# led-heart.net
KiCad netlist of a schematic drawn in EAGLE
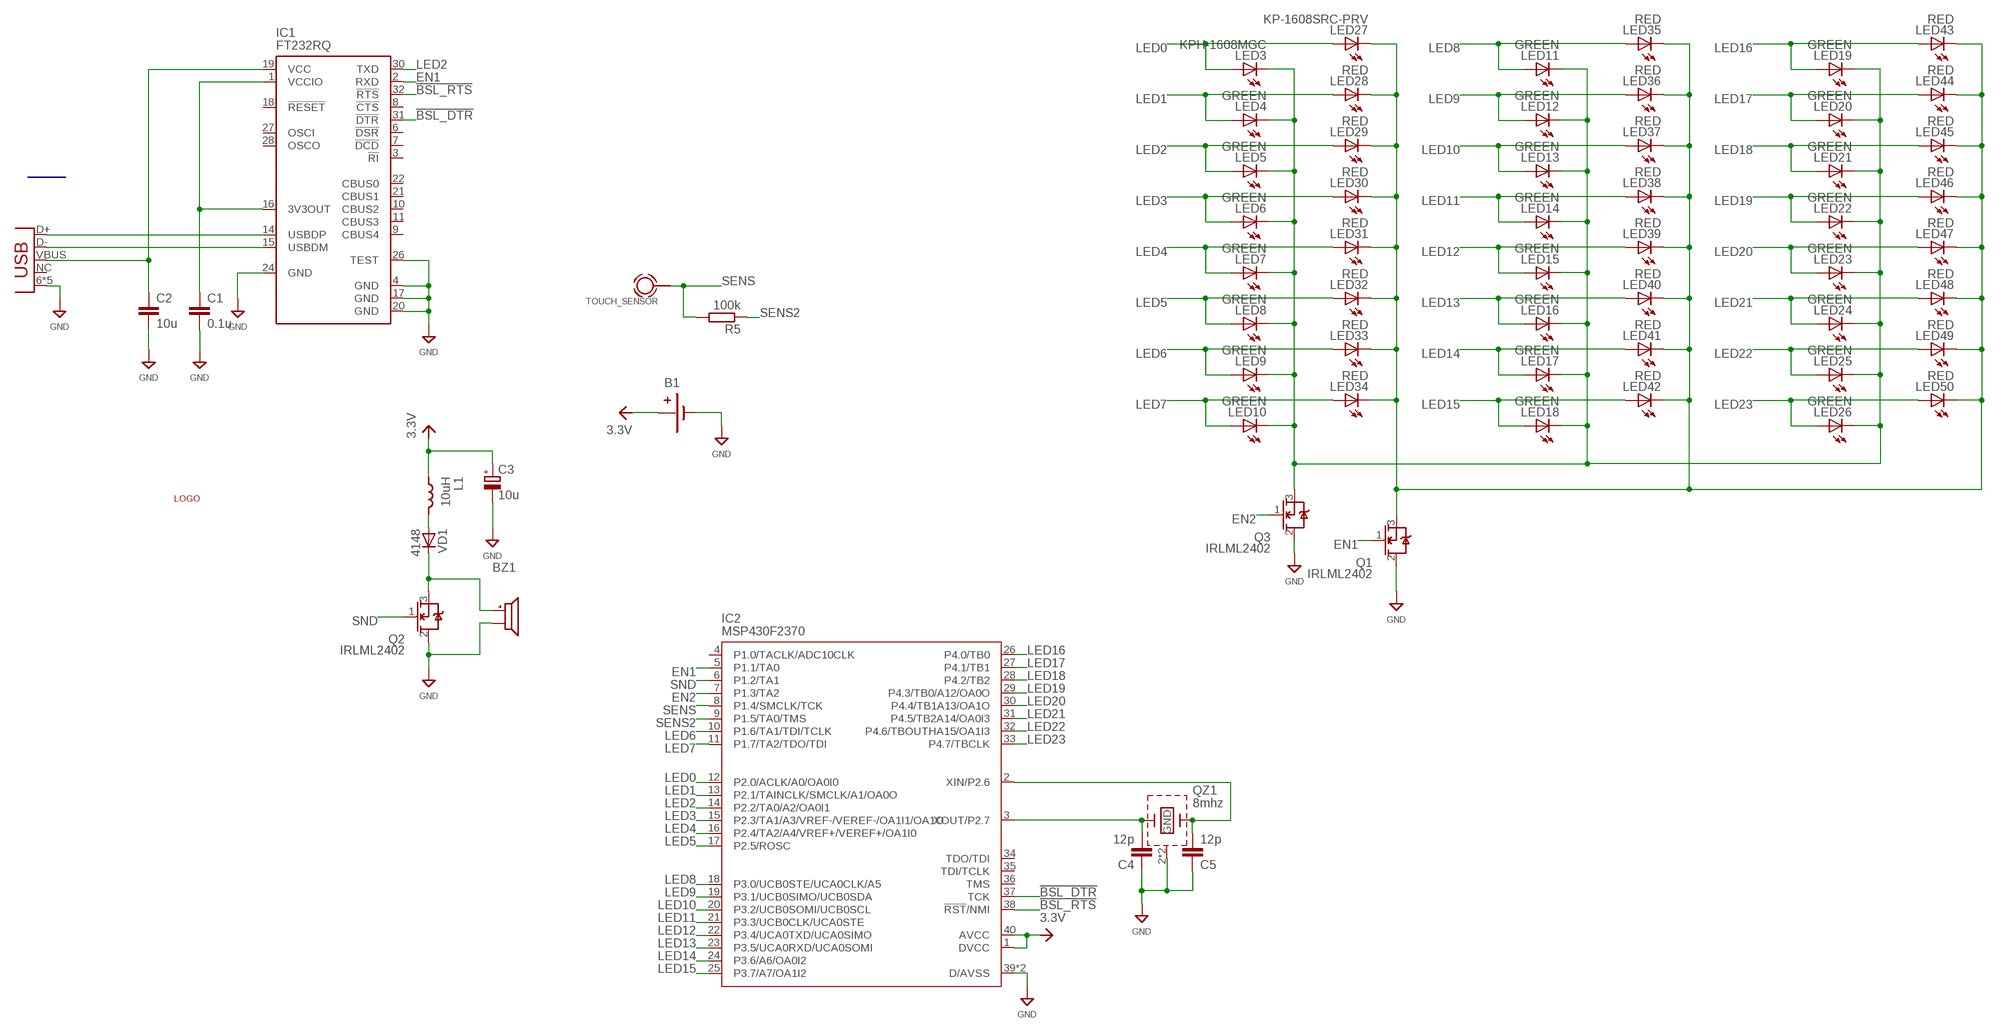
[diagram p0: schematic, sheet 1]

(export (version "E")
  (design (tool "Eeschema 10.0.6"))
  (components
    (comp (ref "B1")
      (value "CR2032")
      (footprint "eagle-import:CR2032")
      (libsource (lib "eagle-import") (part "CR2032"))
    )
    (comp (ref "BZ1")
      (value "BUZZERHYG2575")
      (footprint "eagle-import:HYG7525")
      (libsource (lib "eagle-import") (part "BUZZERHYG2575"))
    )
    (comp (ref "C1")
      (value "0.1u")
      (footprint "eagle-import:R0402")
      (libsource (lib "eagle-import") (part "CAP0402"))
    )
    (comp (ref "C2")
      (value "10u")
      (footprint "eagle-import:R0603")
      (libsource (lib "eagle-import") (part "CAP0603"))
    )
    (comp (ref "C3")
      (value "10u")
      (footprint "eagle-import:SMC_A")
      (libsource (lib "eagle-import") (part "CPOL-EUSMCA"))
    )
    (comp (ref "C4")
      (value "12p")
      (footprint "eagle-import:R0402")
      (libsource (lib "eagle-import") (part "CAP0402"))
    )
    (comp (ref "C5")
      (value "12p")
      (footprint "eagle-import:R0402")
      (libsource (lib "eagle-import") (part "CAP0402"))
    )
    (comp (ref "IC1")
      (value "FT232RQ")
      (footprint "eagle-import:QFN32")
      (libsource (lib "eagle-import") (part "FT232RQ"))
    )
    (comp (ref "IC2")
      (value "MSP430F2370")
      (footprint "eagle-import:QFN40-6X6")
      (libsource (lib "eagle-import") (part "MSP430F2370"))
    )
    (comp (ref "L1")
      (value "10uH")
      (footprint "eagle-import:C1812")
      (libsource (lib "eagle-import") (part "L-1812"))
    )
    (comp (ref "LED3")
      (value "KPH-1608MGC")
      (footprint "eagle-import:LED0603")
      (libsource (lib "eagle-import") (part "LED0603"))
    )
    (comp (ref "LED4")
      (value "GREEN")
      (footprint "eagle-import:LED0603")
      (libsource (lib "eagle-import") (part "LED0603"))
    )
    (comp (ref "LED5")
      (value "GREEN")
      (footprint "eagle-import:LED0603")
      (libsource (lib "eagle-import") (part "LED0603"))
    )
    (comp (ref "LED6")
      (value "GREEN")
      (footprint "eagle-import:LED0603")
      (libsource (lib "eagle-import") (part "LED0603"))
    )
    (comp (ref "LED7")
      (value "GREEN")
      (footprint "eagle-import:LED0603")
      (libsource (lib "eagle-import") (part "LED0603"))
    )
    (comp (ref "LED8")
      (value "GREEN")
      (footprint "eagle-import:LED0603")
      (libsource (lib "eagle-import") (part "LED0603"))
    )
    (comp (ref "LED9")
      (value "GREEN")
      (footprint "eagle-import:LED0603")
      (libsource (lib "eagle-import") (part "LED0603"))
    )
    (comp (ref "LED10")
      (value "GREEN")
      (footprint "eagle-import:LED0603")
      (libsource (lib "eagle-import") (part "LED0603"))
    )
    (comp (ref "LED11")
      (value "GREEN")
      (footprint "eagle-import:LED0603")
      (libsource (lib "eagle-import") (part "LED0603"))
    )
    (comp (ref "LED12")
      (value "GREEN")
      (footprint "eagle-import:LED0603")
      (libsource (lib "eagle-import") (part "LED0603"))
    )
    (comp (ref "LED13")
      (value "GREEN")
      (footprint "eagle-import:LED0603")
      (libsource (lib "eagle-import") (part "LED0603"))
    )
    (comp (ref "LED14")
      (value "GREEN")
      (footprint "eagle-import:LED0603")
      (libsource (lib "eagle-import") (part "LED0603"))
    )
    (comp (ref "LED15")
      (value "GREEN")
      (footprint "eagle-import:LED0603")
      (libsource (lib "eagle-import") (part "LED0603"))
    )
    (comp (ref "LED16")
      (value "GREEN")
      (footprint "eagle-import:LED0603")
      (libsource (lib "eagle-import") (part "LED0603"))
    )
    (comp (ref "LED17")
      (value "GREEN")
      (footprint "eagle-import:LED0603")
      (libsource (lib "eagle-import") (part "LED0603"))
    )
    (comp (ref "LED18")
      (value "GREEN")
      (footprint "eagle-import:LED0603")
      (libsource (lib "eagle-import") (part "LED0603"))
    )
    (comp (ref "LED19")
      (value "GREEN")
      (footprint "eagle-import:LED0603")
      (libsource (lib "eagle-import") (part "LED0603"))
    )
    (comp (ref "LED20")
      (value "GREEN")
      (footprint "eagle-import:LED0603")
      (libsource (lib "eagle-import") (part "LED0603"))
    )
    (comp (ref "LED21")
      (value "GREEN")
      (footprint "eagle-import:LED0603")
      (libsource (lib "eagle-import") (part "LED0603"))
    )
    (comp (ref "LED22")
      (value "GREEN")
      (footprint "eagle-import:LED0603")
      (libsource (lib "eagle-import") (part "LED0603"))
    )
    (comp (ref "LED23")
      (value "GREEN")
      (footprint "eagle-import:LED0603")
      (libsource (lib "eagle-import") (part "LED0603"))
    )
    (comp (ref "LED24")
      (value "GREEN")
      (footprint "eagle-import:LED0603")
      (libsource (lib "eagle-import") (part "LED0603"))
    )
    (comp (ref "LED25")
      (value "GREEN")
      (footprint "eagle-import:LED0603")
      (libsource (lib "eagle-import") (part "LED0603"))
    )
    (comp (ref "LED26")
      (value "GREEN")
      (footprint "eagle-import:LED0603")
      (libsource (lib "eagle-import") (part "LED0603"))
    )
    (comp (ref "LED27")
      (value "KP-1608SRC-PRV")
      (footprint "eagle-import:LED0603")
      (libsource (lib "eagle-import") (part "LED0603"))
    )
    (comp (ref "LED28")
      (value "RED")
      (footprint "eagle-import:LED0603")
      (libsource (lib "eagle-import") (part "LED0603"))
    )
    (comp (ref "LED29")
      (value "RED")
      (footprint "eagle-import:LED0603")
      (libsource (lib "eagle-import") (part "LED0603"))
    )
    (comp (ref "LED30")
      (value "RED")
      (footprint "eagle-import:LED0603")
      (libsource (lib "eagle-import") (part "LED0603"))
    )
    (comp (ref "LED31")
      (value "RED")
      (footprint "eagle-import:LED0603")
      (libsource (lib "eagle-import") (part "LED0603"))
    )
    (comp (ref "LED32")
      (value "RED")
      (footprint "eagle-import:LED0603")
      (libsource (lib "eagle-import") (part "LED0603"))
    )
    (comp (ref "LED33")
      (value "RED")
      (footprint "eagle-import:LED0603")
      (libsource (lib "eagle-import") (part "LED0603"))
    )
    (comp (ref "LED34")
      (value "RED")
      (footprint "eagle-import:LED0603")
      (libsource (lib "eagle-import") (part "LED0603"))
    )
    (comp (ref "LED35")
      (value "RED")
      (footprint "eagle-import:LED0603")
      (libsource (lib "eagle-import") (part "LED0603"))
    )
    (comp (ref "LED36")
      (value "RED")
      (footprint "eagle-import:LED0603")
      (libsource (lib "eagle-import") (part "LED0603"))
    )
    (comp (ref "LED37")
      (value "RED")
      (footprint "eagle-import:LED0603")
      (libsource (lib "eagle-import") (part "LED0603"))
    )
    (comp (ref "LED38")
      (value "RED")
      (footprint "eagle-import:LED0603")
      (libsource (lib "eagle-import") (part "LED0603"))
    )
    (comp (ref "LED39")
      (value "RED")
      (footprint "eagle-import:LED0603")
      (libsource (lib "eagle-import") (part "LED0603"))
    )
    (comp (ref "LED40")
      (value "RED")
      (footprint "eagle-import:LED0603")
      (libsource (lib "eagle-import") (part "LED0603"))
    )
    (comp (ref "LED41")
      (value "RED")
      (footprint "eagle-import:LED0603")
      (libsource (lib "eagle-import") (part "LED0603"))
    )
    (comp (ref "LED42")
      (value "RED")
      (footprint "eagle-import:LED0603")
      (libsource (lib "eagle-import") (part "LED0603"))
    )
    (comp (ref "LED43")
      (value "RED")
      (footprint "eagle-import:LED0603")
      (libsource (lib "eagle-import") (part "LED0603"))
    )
    (comp (ref "LED44")
      (value "RED")
      (footprint "eagle-import:LED0603")
      (libsource (lib "eagle-import") (part "LED0603"))
    )
    (comp (ref "LED45")
      (value "RED")
      (footprint "eagle-import:LED0603")
      (libsource (lib "eagle-import") (part "LED0603"))
    )
    (comp (ref "LED46")
      (value "RED")
      (footprint "eagle-import:LED0603")
      (libsource (lib "eagle-import") (part "LED0603"))
    )
    (comp (ref "LED47")
      (value "RED")
      (footprint "eagle-import:LED0603")
      (libsource (lib "eagle-import") (part "LED0603"))
    )
    (comp (ref "LED48")
      (value "RED")
      (footprint "eagle-import:LED0603")
      (libsource (lib "eagle-import") (part "LED0603"))
    )
    (comp (ref "LED49")
      (value "RED")
      (footprint "eagle-import:LED0603")
      (libsource (lib "eagle-import") (part "LED0603"))
    )
    (comp (ref "LED50")
      (value "RED")
      (footprint "eagle-import:LED0603")
      (libsource (lib "eagle-import") (part "LED0603"))
    )
    (comp (ref "LOGO1")
      (value "LOGO2")
      (footprint "eagle-import:LOGO2")
      (libsource (lib "eagle-import") (part "LOGO2"))
    )
    (comp (ref "Q1")
      (value "IRLML2402")
      (footprint "eagle-import:SOT23")
      (libsource (lib "eagle-import") (part "MOSFET_NSOT23"))
    )
    (comp (ref "Q2")
      (value "IRLML2402")
      (footprint "eagle-import:SOT23")
      (libsource (lib "eagle-import") (part "MOSFET_NSOT23"))
    )
    (comp (ref "Q3")
      (value "IRLML2402")
      (footprint "eagle-import:SOT23")
      (libsource (lib "eagle-import") (part "MOSFET_NSOT23"))
    )
    (comp (ref "QZ1")
      (value "8mhz")
      (footprint "eagle-import:3225")
      (libsource (lib "eagle-import") (part "QUARTZ_GND3225"))
    )
    (comp (ref "R5")
      (value "100k")
      (footprint "eagle-import:R0402")
      (libsource (lib "eagle-import") (part "RESR0402"))
    )
    (comp (ref "U$1")
      (value "TOUCH_SENSOR")
      (footprint "eagle-import:TOUCH_SENSOR")
      (libsource (lib "eagle-import") (part "TOUCH_SENSOR"))
    )
    (comp (ref "VD1")
      (value "4148")
      (footprint "eagle-import:SOD123")
      (libsource (lib "eagle-import") (part "DIODE-SOD123"))
    )
    (comp (ref "X1")
      (value "USBMICRO_B")
      (footprint "eagle-import:USB_MICROB")
      (libsource (lib "eagle-import") (part "USBMICRO_B"))
    )
  )
  (nets
    (net (code "1") (name "/EN1") (class "Default")
      (node (ref "IC1") (pin "2") (pinfunction "RXD_2") (pintype "input"))
      (node (ref "IC2") (pin "5") (pinfunction "P1.1/TA0_5") (pintype "bidirectional"))
      (node (ref "Q1") (pin "1") (pinfunction "G_1") (pintype "bidirectional"))
    )
    (net (code "2") (name "/EN2") (class "Default")
      (node (ref "IC2") (pin "7") (pinfunction "P1.3/TA2_7") (pintype "bidirectional"))
      (node (ref "Q3") (pin "1") (pinfunction "G_1") (pintype "bidirectional"))
    )
    (net (code "3") (name "/LED0") (class "Default")
      (node (ref "IC2") (pin "12") (pinfunction "P2.0/ACLK/A0/OA0I0_12") (pintype "bidirectional"))
      (node (ref "LED27") (pin "A") (pinfunction "A_A") (pintype "passive"))
      (node (ref "LED3") (pin "A") (pinfunction "A_A") (pintype "passive"))
    )
    (net (code "4") (name "/LED1") (class "Default")
      (node (ref "IC2") (pin "13") (pinfunction "P2.1/TAINCLK/SMCLK/A1/OA0O_13") (pintype "bidirectional"))
      (node (ref "LED28") (pin "A") (pinfunction "A_A") (pintype "passive"))
      (node (ref "LED4") (pin "A") (pinfunction "A_A") (pintype "passive"))
    )
    (net (code "5") (name "/LED2") (class "Default")
      (node (ref "IC1") (pin "30") (pinfunction "TXD_30") (pintype "output"))
      (node (ref "IC2") (pin "14") (pinfunction "P2.2/TA0/A2/OA0I1_14") (pintype "bidirectional"))
      (node (ref "LED29") (pin "A") (pinfunction "A_A") (pintype "passive"))
      (node (ref "LED5") (pin "A") (pinfunction "A_A") (pintype "passive"))
    )
    (net (code "6") (name "/LED3") (class "Default")
      (node (ref "IC2") (pin "15") (pinfunction "P2.3/TA1/A3/VREF-/VEREF-/OA1I1/OA1O_15") (pintype "bidirectional"))
      (node (ref "LED30") (pin "A") (pinfunction "A_A") (pintype "passive"))
      (node (ref "LED6") (pin "A") (pinfunction "A_A") (pintype "passive"))
    )
    (net (code "7") (name "/LED4") (class "Default")
      (node (ref "IC2") (pin "16") (pinfunction "P2.4/TA2/A4/VREF+/VEREF+/OA1I0_16") (pintype "bidirectional"))
      (node (ref "LED31") (pin "A") (pinfunction "A_A") (pintype "passive"))
      (node (ref "LED7") (pin "A") (pinfunction "A_A") (pintype "passive"))
    )
    (net (code "8") (name "/LED5") (class "Default")
      (node (ref "IC2") (pin "17") (pinfunction "P2.5/ROSC_17") (pintype "bidirectional"))
      (node (ref "LED32") (pin "A") (pinfunction "A_A") (pintype "passive"))
      (node (ref "LED8") (pin "A") (pinfunction "A_A") (pintype "passive"))
    )
    (net (code "9") (name "/LED6") (class "Default")
      (node (ref "IC2") (pin "10") (pinfunction "P1.6/TA1/TDI/TCLK_10") (pintype "bidirectional"))
      (node (ref "LED33") (pin "A") (pinfunction "A_A") (pintype "passive"))
      (node (ref "LED9") (pin "A") (pinfunction "A_A") (pintype "passive"))
    )
    (net (code "10") (name "/LED7") (class "Default")
      (node (ref "IC2") (pin "11") (pinfunction "P1.7/TA2/TDO/TDI_11") (pintype "bidirectional"))
      (node (ref "LED10") (pin "A") (pinfunction "A_A") (pintype "passive"))
      (node (ref "LED34") (pin "A") (pinfunction "A_A") (pintype "passive"))
    )
    (net (code "11") (name "/LED8") (class "Default")
      (node (ref "IC2") (pin "18") (pinfunction "P3.0/UCB0STE/UCA0CLK/A5_18") (pintype "bidirectional"))
      (node (ref "LED11") (pin "A") (pinfunction "A_A") (pintype "passive"))
      (node (ref "LED35") (pin "A") (pinfunction "A_A") (pintype "passive"))
    )
    (net (code "12") (name "/LED9") (class "Default")
      (node (ref "IC2") (pin "19") (pinfunction "P3.1/UCB0SIMO/UCB0SDA_19") (pintype "bidirectional"))
      (node (ref "LED12") (pin "A") (pinfunction "A_A") (pintype "passive"))
      (node (ref "LED36") (pin "A") (pinfunction "A_A") (pintype "passive"))
    )
    (net (code "13") (name "/LED10") (class "Default")
      (node (ref "IC2") (pin "20") (pinfunction "P3.2/UCB0SOMI/UCB0SCL_20") (pintype "bidirectional"))
      (node (ref "LED13") (pin "A") (pinfunction "A_A") (pintype "passive"))
      (node (ref "LED37") (pin "A") (pinfunction "A_A") (pintype "passive"))
    )
    (net (code "14") (name "/LED11") (class "Default")
      (node (ref "IC2") (pin "21") (pinfunction "P3.3/UCB0CLK/UCA0STE_21") (pintype "bidirectional"))
      (node (ref "LED14") (pin "A") (pinfunction "A_A") (pintype "passive"))
      (node (ref "LED38") (pin "A") (pinfunction "A_A") (pintype "passive"))
    )
    (net (code "15") (name "/LED12") (class "Default")
      (node (ref "IC2") (pin "22") (pinfunction "P3.4/UCA0TXD/UCA0SIMO_22") (pintype "bidirectional"))
      (node (ref "LED15") (pin "A") (pinfunction "A_A") (pintype "passive"))
      (node (ref "LED39") (pin "A") (pinfunction "A_A") (pintype "passive"))
    )
    (net (code "16") (name "/LED13") (class "Default")
      (node (ref "IC2") (pin "23") (pinfunction "P3.5/UCA0RXD/UCA0SOMI_23") (pintype "bidirectional"))
      (node (ref "LED16") (pin "A") (pinfunction "A_A") (pintype "passive"))
      (node (ref "LED40") (pin "A") (pinfunction "A_A") (pintype "passive"))
    )
    (net (code "17") (name "/LED14") (class "Default")
      (node (ref "IC2") (pin "24") (pinfunction "P3.6/A6/OA0I2_24") (pintype "bidirectional"))
      (node (ref "LED17") (pin "A") (pinfunction "A_A") (pintype "passive"))
      (node (ref "LED41") (pin "A") (pinfunction "A_A") (pintype "passive"))
    )
    (net (code "18") (name "/LED15") (class "Default")
      (node (ref "IC2") (pin "25") (pinfunction "P3.7/A7/OA1I2_25") (pintype "bidirectional"))
      (node (ref "LED18") (pin "A") (pinfunction "A_A") (pintype "passive"))
      (node (ref "LED42") (pin "A") (pinfunction "A_A") (pintype "passive"))
    )
    (net (code "19") (name "/LED16") (class "Default")
      (node (ref "IC2") (pin "26") (pinfunction "P4.0/TB0_26") (pintype "bidirectional"))
      (node (ref "LED19") (pin "A") (pinfunction "A_A") (pintype "passive"))
      (node (ref "LED43") (pin "A") (pinfunction "A_A") (pintype "passive"))
    )
    (net (code "20") (name "/LED17") (class "Default")
      (node (ref "IC2") (pin "27") (pinfunction "P4.1/TB1_27") (pintype "bidirectional"))
      (node (ref "LED20") (pin "A") (pinfunction "A_A") (pintype "passive"))
      (node (ref "LED44") (pin "A") (pinfunction "A_A") (pintype "passive"))
    )
    (net (code "21") (name "/LED18") (class "Default")
      (node (ref "IC2") (pin "28") (pinfunction "P4.2/TB2_28") (pintype "bidirectional"))
      (node (ref "LED21") (pin "A") (pinfunction "A_A") (pintype "passive"))
      (node (ref "LED45") (pin "A") (pinfunction "A_A") (pintype "passive"))
    )
    (net (code "22") (name "/LED19") (class "Default")
      (node (ref "IC2") (pin "29") (pinfunction "P4.3/TB0/A12/OA0O_29") (pintype "bidirectional"))
      (node (ref "LED22") (pin "A") (pinfunction "A_A") (pintype "passive"))
      (node (ref "LED46") (pin "A") (pinfunction "A_A") (pintype "passive"))
    )
    (net (code "23") (name "/LED20") (class "Default")
      (node (ref "IC2") (pin "30") (pinfunction "P4.4/TB1A13/OA1O_30") (pintype "bidirectional"))
      (node (ref "LED23") (pin "A") (pinfunction "A_A") (pintype "passive"))
      (node (ref "LED47") (pin "A") (pinfunction "A_A") (pintype "passive"))
    )
    (net (code "24") (name "/LED21") (class "Default")
      (node (ref "IC2") (pin "31") (pinfunction "P4.5/TB2A14/OA0I3_31") (pintype "bidirectional"))
      (node (ref "LED24") (pin "A") (pinfunction "A_A") (pintype "passive"))
      (node (ref "LED48") (pin "A") (pinfunction "A_A") (pintype "passive"))
    )
    (net (code "25") (name "/LED22") (class "Default")
      (node (ref "IC2") (pin "32") (pinfunction "P4.6/TBOUTHA15/OA1I3_32") (pintype "bidirectional"))
      (node (ref "LED25") (pin "A") (pinfunction "A_A") (pintype "passive"))
      (node (ref "LED49") (pin "A") (pinfunction "A_A") (pintype "passive"))
    )
    (net (code "26") (name "/LED23") (class "Default")
      (node (ref "IC2") (pin "33") (pinfunction "P4.7/TBCLK_33") (pintype "bidirectional"))
      (node (ref "LED26") (pin "A") (pinfunction "A_A") (pintype "passive"))
      (node (ref "LED50") (pin "A") (pinfunction "A_A") (pintype "passive"))
    )
    (net (code "27") (name "/SENS") (class "Default")
      (node (ref "IC2") (pin "8") (pinfunction "P1.4/SMCLK/TCK_8") (pintype "bidirectional"))
      (node (ref "R5") (pin "2") (pinfunction "2_2") (pintype "passive"))
      (node (ref "U$1") (pin "CON") (pinfunction "CON_CON") (pintype "bidirectional"))
    )
    (net (code "28") (name "/SENS2") (class "Default")
      (node (ref "IC2") (pin "9") (pinfunction "P1.5/TA0/TMS_9") (pintype "bidirectional"))
      (node (ref "R5") (pin "1") (pinfunction "1_1") (pintype "passive"))
    )
    (net (code "29") (name "/SND") (class "Default")
      (node (ref "IC2") (pin "6") (pinfunction "P1.2/TA1_6") (pintype "bidirectional"))
      (node (ref "Q2") (pin "1") (pinfunction "G_1") (pintype "bidirectional"))
    )
    (net (code "30") (name "/~{BSL_DTR}") (class "Default")
      (node (ref "IC1") (pin "31") (pinfunction "~{DTR}_31") (pintype "output"))
      (node (ref "IC2") (pin "37") (pinfunction "TCK_37") (pintype "bidirectional"))
    )
    (net (code "31") (name "/~{BSL_RTS}") (class "Default")
      (node (ref "IC1") (pin "32") (pinfunction "~{RTS}_32") (pintype "output"))
      (node (ref "IC2") (pin "38") (pinfunction "~{RST}/NMI_38") (pintype "input"))
    )
    (net (code "32") (name "3.3V") (class "Default")
      (node (ref "B1") (pin "PLUS") (pinfunction "PLUS_PLUS") (pintype "power_in"))
      (node (ref "C3") (pin "+") (pinfunction "+_+") (pintype "passive"))
      (node (ref "IC2") (pin "1") (pinfunction "DVCC_1") (pintype "power_in"))
      (node (ref "IC2") (pin "40") (pinfunction "AVCC_40") (pintype "power_in"))
      (node (ref "L1") (pin "1") (pinfunction "P$1_1") (pintype "bidirectional"))
    )
    (net (code "33") (name "GND") (class "Default")
      (node (ref "B1") (pin "MINUS") (pinfunction "MINUS_MINUS") (pintype "power_in"))
      (node (ref "BZ1") (pin "2") (pinfunction "M_2") (pintype "bidirectional"))
      (node (ref "C1") (pin "2") (pinfunction "2_2") (pintype "passive"))
      (node (ref "C2") (pin "2") (pinfunction "2_2") (pintype "passive"))
      (node (ref "C3") (pin "-") (pinfunction "-_-") (pintype "passive"))
      (node (ref "C4") (pin "1") (pinfunction "1_1") (pintype "passive"))
      (node (ref "C5") (pin "1") (pinfunction "1_1") (pintype "passive"))
      (node (ref "IC1") (pin "17") (pinfunction "GND_17") (pintype "power_in"))
      (node (ref "IC1") (pin "20") (pinfunction "GND_20") (pintype "power_in"))
      (node (ref "IC1") (pin "24") (pinfunction "GND_24") (pintype "power_in"))
      (node (ref "IC1") (pin "26") (pinfunction "TEST_26") (pintype "input"))
      (node (ref "IC1") (pin "4") (pinfunction "GND_4") (pintype "power_in"))
      (node (ref "IC2") (pin "39") (pinfunction "D/AVSS_39") (pintype "power_in"))
      (node (ref "IC2") (pin "EXP") (pinfunction "D/AVSS_EXP") (pintype "power_in"))
      (node (ref "Q1") (pin "2") (pinfunction "S_2") (pintype "bidirectional"))
      (node (ref "Q2") (pin "2") (pinfunction "S_2") (pintype "bidirectional"))
      (node (ref "Q3") (pin "2") (pinfunction "S_2") (pintype "bidirectional"))
      (node (ref "QZ1") (pin "2") (pinfunction "GND_2") (pintype "bidirectional"))
      (node (ref "QZ1") (pin "4") (pinfunction "GND_4") (pintype "bidirectional"))
      (node (ref "X1") (pin "6") (pinfunction "GND_6") (pintype "bidirectional"))
      (node (ref "X1") (pin "7") (pinfunction "GND_7") (pintype "bidirectional"))
      (node (ref "X1") (pin "8") (pinfunction "GND_8") (pintype "bidirectional"))
      (node (ref "X1") (pin "9") (pinfunction "GND_9") (pintype "bidirectional"))
      (node (ref "X1") (pin "GND") (pinfunction "GND_GND") (pintype "bidirectional"))
    )
    (net (code "34") (name "Net-(BZ1-P)") (class "Default")
      (node (ref "BZ1") (pin "1") (pinfunction "P_1") (pintype "bidirectional"))
      (node (ref "Q2") (pin "3") (pinfunction "D_3") (pintype "bidirectional"))
      (node (ref "VD1") (pin "C") (pinfunction "C_C") (pintype "passive"))
    )
    (net (code "35") (name "Net-(IC1-3V3OUT)") (class "Default")
      (node (ref "C1") (pin "1") (pinfunction "1_1") (pintype "passive"))
      (node (ref "IC1") (pin "1") (pinfunction "VCCIO_1") (pintype "power_in"))
      (node (ref "IC1") (pin "16") (pinfunction "3V3OUT_16") (pintype "output"))
    )
    (net (code "36") (name "Net-(IC1-USBDM)") (class "Default")
      (node (ref "IC1") (pin "15") (pinfunction "USBDM_15") (pintype "bidirectional"))
      (node (ref "X1") (pin "D-") (pinfunction "D-_D-") (pintype "bidirectional"))
    )
    (net (code "37") (name "Net-(IC1-USBDP)") (class "Default")
      (node (ref "IC1") (pin "14") (pinfunction "USBDP_14") (pintype "bidirectional"))
      (node (ref "X1") (pin "D+") (pinfunction "D+_D+") (pintype "bidirectional"))
    )
    (net (code "38") (name "Net-(IC1-VCC)") (class "Default")
      (node (ref "C2") (pin "1") (pinfunction "1_1") (pintype "passive"))
      (node (ref "IC1") (pin "19") (pinfunction "VCC_19") (pintype "power_in"))
      (node (ref "X1") (pin "VBUS") (pinfunction "VBUS_VBUS") (pintype "bidirectional"))
    )
    (net (code "39") (name "Net-(IC2-XIN{slash}P2.6)") (class "Default")
      (node (ref "C5") (pin "2") (pinfunction "2_2") (pintype "passive"))
      (node (ref "IC2") (pin "2") (pinfunction "XIN/P2.6_2") (pintype "bidirectional"))
      (node (ref "QZ1") (pin "1") (pinfunction "1_1") (pintype "bidirectional"))
    )
    (net (code "40") (name "Net-(IC2-XOUT{slash}P2.7)") (class "Default")
      (node (ref "C4") (pin "2") (pinfunction "2_2") (pintype "passive"))
      (node (ref "IC2") (pin "3") (pinfunction "XOUT/P2.7_3") (pintype "bidirectional"))
      (node (ref "QZ1") (pin "3") (pinfunction "2_3") (pintype "bidirectional"))
    )
    (net (code "41") (name "Net-(L1-P$2)") (class "Default")
      (node (ref "L1") (pin "2") (pinfunction "P$2_2") (pintype "bidirectional"))
      (node (ref "VD1") (pin "A") (pinfunction "A_A") (pintype "passive"))
    )
    (net (code "42") (name "Net-(Q1-D)") (class "Default")
      (node (ref "LED27") (pin "C") (pinfunction "C_C") (pintype "passive"))
      (node (ref "LED28") (pin "C") (pinfunction "C_C") (pintype "passive"))
      (node (ref "LED29") (pin "C") (pinfunction "C_C") (pintype "passive"))
      (node (ref "LED30") (pin "C") (pinfunction "C_C") (pintype "passive"))
      (node (ref "LED31") (pin "C") (pinfunction "C_C") (pintype "passive"))
      (node (ref "LED32") (pin "C") (pinfunction "C_C") (pintype "passive"))
      (node (ref "LED33") (pin "C") (pinfunction "C_C") (pintype "passive"))
      (node (ref "LED34") (pin "C") (pinfunction "C_C") (pintype "passive"))
      (node (ref "LED35") (pin "C") (pinfunction "C_C") (pintype "passive"))
      (node (ref "LED36") (pin "C") (pinfunction "C_C") (pintype "passive"))
      (node (ref "LED37") (pin "C") (pinfunction "C_C") (pintype "passive"))
      (node (ref "LED38") (pin "C") (pinfunction "C_C") (pintype "passive"))
      (node (ref "LED39") (pin "C") (pinfunction "C_C") (pintype "passive"))
      (node (ref "LED40") (pin "C") (pinfunction "C_C") (pintype "passive"))
      (node (ref "LED41") (pin "C") (pinfunction "C_C") (pintype "passive"))
      (node (ref "LED42") (pin "C") (pinfunction "C_C") (pintype "passive"))
      (node (ref "LED43") (pin "C") (pinfunction "C_C") (pintype "passive"))
      (node (ref "LED44") (pin "C") (pinfunction "C_C") (pintype "passive"))
      (node (ref "LED45") (pin "C") (pinfunction "C_C") (pintype "passive"))
      (node (ref "LED46") (pin "C") (pinfunction "C_C") (pintype "passive"))
      (node (ref "LED47") (pin "C") (pinfunction "C_C") (pintype "passive"))
      (node (ref "LED48") (pin "C") (pinfunction "C_C") (pintype "passive"))
      (node (ref "LED49") (pin "C") (pinfunction "C_C") (pintype "passive"))
      (node (ref "LED50") (pin "C") (pinfunction "C_C") (pintype "passive"))
      (node (ref "Q1") (pin "3") (pinfunction "D_3") (pintype "bidirectional"))
    )
    (net (code "43") (name "Net-(Q3-D)") (class "Default")
      (node (ref "LED10") (pin "C") (pinfunction "C_C") (pintype "passive"))
      (node (ref "LED11") (pin "C") (pinfunction "C_C") (pintype "passive"))
      (node (ref "LED12") (pin "C") (pinfunction "C_C") (pintype "passive"))
      (node (ref "LED13") (pin "C") (pinfunction "C_C") (pintype "passive"))
      (node (ref "LED14") (pin "C") (pinfunction "C_C") (pintype "passive"))
      (node (ref "LED15") (pin "C") (pinfunction "C_C") (pintype "passive"))
      (node (ref "LED16") (pin "C") (pinfunction "C_C") (pintype "passive"))
      (node (ref "LED17") (pin "C") (pinfunction "C_C") (pintype "passive"))
      (node (ref "LED18") (pin "C") (pinfunction "C_C") (pintype "passive"))
      (node (ref "LED19") (pin "C") (pinfunction "C_C") (pintype "passive"))
      (node (ref "LED20") (pin "C") (pinfunction "C_C") (pintype "passive"))
      (node (ref "LED21") (pin "C") (pinfunction "C_C") (pintype "passive"))
      (node (ref "LED22") (pin "C") (pinfunction "C_C") (pintype "passive"))
      (node (ref "LED23") (pin "C") (pinfunction "C_C") (pintype "passive"))
      (node (ref "LED24") (pin "C") (pinfunction "C_C") (pintype "passive"))
      (node (ref "LED25") (pin "C") (pinfunction "C_C") (pintype "passive"))
      (node (ref "LED26") (pin "C") (pinfunction "C_C") (pintype "passive"))
      (node (ref "LED3") (pin "C") (pinfunction "C_C") (pintype "passive"))
      (node (ref "LED4") (pin "C") (pinfunction "C_C") (pintype "passive"))
      (node (ref "LED5") (pin "C") (pinfunction "C_C") (pintype "passive"))
      (node (ref "LED6") (pin "C") (pinfunction "C_C") (pintype "passive"))
      (node (ref "LED7") (pin "C") (pinfunction "C_C") (pintype "passive"))
      (node (ref "LED8") (pin "C") (pinfunction "C_C") (pintype "passive"))
      (node (ref "LED9") (pin "C") (pinfunction "C_C") (pintype "passive"))
      (node (ref "Q3") (pin "3") (pinfunction "D_3") (pintype "bidirectional"))
    )
    (net (code "44") (name "unconnected-(IC1-CBUS0-Pad22)") (class "Default")
      (node (ref "IC1") (pin "22") (pinfunction "CBUS0_22") (pintype "bidirectional"))
    )
    (net (code "45") (name "unconnected-(IC1-CBUS1-Pad21)") (class "Default")
      (node (ref "IC1") (pin "21") (pinfunction "CBUS1_21") (pintype "bidirectional"))
    )
    (net (code "46") (name "unconnected-(IC1-CBUS2-Pad10)") (class "Default")
      (node (ref "IC1") (pin "10") (pinfunction "CBUS2_10") (pintype "bidirectional"))
    )
    (net (code "47") (name "unconnected-(IC1-CBUS3-Pad11)") (class "Default")
      (node (ref "IC1") (pin "11") (pinfunction "CBUS3_11") (pintype "bidirectional"))
    )
    (net (code "48") (name "unconnected-(IC1-CBUS4-Pad9)") (class "Default")
      (node (ref "IC1") (pin "9") (pinfunction "CBUS4_9") (pintype "bidirectional"))
    )
    (net (code "49") (name "unconnected-(IC1-OSCI-Pad27)") (class "Default")
      (node (ref "IC1") (pin "27") (pinfunction "OSCI_27") (pintype "input"))
    )
    (net (code "50") (name "unconnected-(IC1-OSCO-Pad28)") (class "Default")
      (node (ref "IC1") (pin "28") (pinfunction "OSCO_28") (pintype "output"))
    )
    (net (code "51") (name "unconnected-(IC1-~{CTS}-Pad8)") (class "Default")
      (node (ref "IC1") (pin "8") (pinfunction "~{CTS}_8") (pintype "input"))
    )
    (net (code "52") (name "unconnected-(IC1-~{DCD}-Pad7)") (class "Default")
      (node (ref "IC1") (pin "7") (pinfunction "~{DCD}_7") (pintype "input"))
    )
    (net (code "53") (name "unconnected-(IC1-~{DSR}-Pad6)") (class "Default")
      (node (ref "IC1") (pin "6") (pinfunction "~{DSR}_6") (pintype "input"))
    )
    (net (code "54") (name "unconnected-(IC1-~{RESET}-Pad18)") (class "Default")
      (node (ref "IC1") (pin "18") (pinfunction "~{RESET}_18") (pintype "input"))
    )
    (net (code "55") (name "unconnected-(IC1-~{RI}-Pad3)") (class "Default")
      (node (ref "IC1") (pin "3") (pinfunction "~{RI}_3") (pintype "input"))
    )
    (net (code "56") (name "unconnected-(IC2-P1.0{slash}TACLK{slash}ADC10CLK-Pad4)") (class "Default")
      (node (ref "IC2") (pin "4") (pinfunction "P1.0/TACLK/ADC10CLK_4") (pintype "bidirectional"))
    )
    (net (code "57") (name "unconnected-(IC2-TDI{slash}TCLK-Pad35)") (class "Default")
      (node (ref "IC2") (pin "35") (pinfunction "TDI/TCLK_35") (pintype "bidirectional"))
    )
    (net (code "58") (name "unconnected-(IC2-TDO{slash}TDI-Pad34)") (class "Default")
      (node (ref "IC2") (pin "34") (pinfunction "TDO/TDI_34") (pintype "input"))
    )
    (net (code "59") (name "unconnected-(IC2-TMS-Pad36)") (class "Default")
      (node (ref "IC2") (pin "36") (pinfunction "TMS_36") (pintype "bidirectional"))
    )
    (net (code "60") (name "unconnected-(X1-PadNC)") (class "Default")
      (node (ref "X1") (pin "NC") (pinfunction "NC_NC") (pintype "bidirectional"))
    )
  )
)
